# CPU.net
KiCad netlist of a schematic drawn in Altium Designer
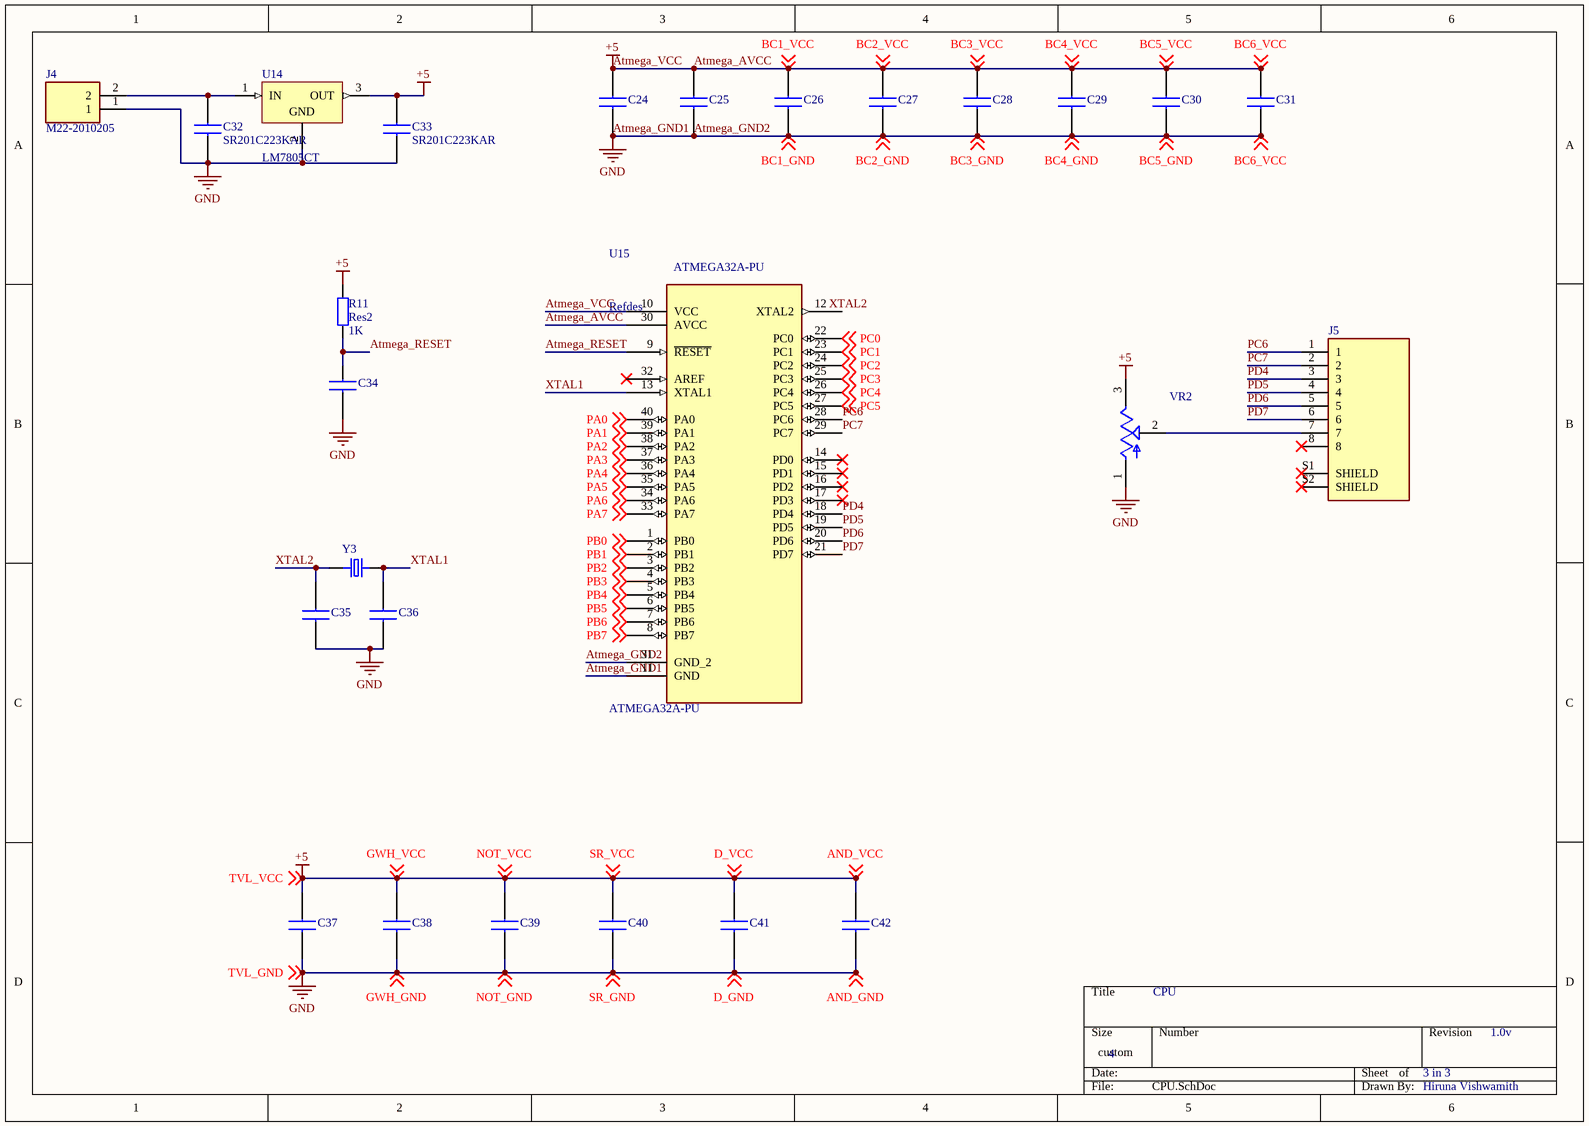
[diagram p0: CPU.SchDoc]

(export (version "E")
  (design (tool "Eeschema 10.0.6"))
  (components
    (comp (ref "C24")
      (value "SR201C223KAR")
      (footprint "AVX-SR20")
      (description "Cap Ceramic 0.022uF 100V X7R 10% Radial 2.54mm 125C Bulk")
      (libsource (lib "SR201C223KAR") (part "SR201C223KAR"))
    )
    (comp (ref "C25")
      (value "SR201C223KAR")
      (footprint "AVX-SR20")
      (description "Cap Ceramic 0.022uF 100V X7R 10% Radial 2.54mm 125C Bulk")
      (libsource (lib "SR201C223KAR") (part "SR201C223KAR"))
    )
    (comp (ref "C26")
      (value "SR201C223KAR")
      (footprint "AVX-SR20")
      (description "Cap Ceramic 0.022uF 100V X7R 10% Radial 2.54mm 125C Bulk")
      (libsource (lib "SR201C223KAR") (part "SR201C223KAR"))
    )
    (comp (ref "C27")
      (value "SR201C223KAR")
      (footprint "AVX-SR20")
      (description "Cap Ceramic 0.022uF 100V X7R 10% Radial 2.54mm 125C Bulk")
      (libsource (lib "SR201C223KAR") (part "SR201C223KAR"))
    )
    (comp (ref "C28")
      (value "SR201C223KAR")
      (footprint "AVX-SR20")
      (description "Cap Ceramic 0.022uF 100V X7R 10% Radial 2.54mm 125C Bulk")
      (libsource (lib "SR201C223KAR") (part "SR201C223KAR"))
    )
    (comp (ref "C29")
      (value "SR201C223KAR")
      (footprint "AVX-SR20")
      (description "Cap Ceramic 0.022uF 100V X7R 10% Radial 2.54mm 125C Bulk")
      (libsource (lib "SR201C223KAR") (part "SR201C223KAR"))
    )
    (comp (ref "C30")
      (value "SR201C223KAR")
      (footprint "AVX-SR20")
      (description "Cap Ceramic 0.022uF 100V X7R 10% Radial 2.54mm 125C Bulk")
      (libsource (lib "SR201C223KAR") (part "SR201C223KAR"))
    )
    (comp (ref "C31")
      (value "SR201C223KAR")
      (footprint "AVX-SR20")
      (description "Cap Ceramic 0.022uF 100V X7R 10% Radial 2.54mm 125C Bulk")
      (libsource (lib "SR201C223KAR") (part "SR201C223KAR"))
    )
    (comp (ref "C32")
      (value "SR201C223KAR")
      (footprint "AVX-SR20")
      (description "Cap Ceramic 0.022uF 100V X7R 10% Radial 2.54mm 125C Bulk")
      (libsource (lib "SR201C223KAR") (part "SR201C223KAR"))
    )
    (comp (ref "C33")
      (value "SR201C223KAR")
      (footprint "AVX-SR20")
      (description "Cap Ceramic 0.022uF 100V X7R 10% Radial 2.54mm 125C Bulk")
      (libsource (lib "SR201C223KAR") (part "SR201C223KAR"))
    )
    (comp (ref "C34")
      (value "SR201C223KAR")
      (footprint "AVX-SR20")
      (description "Cap Ceramic 0.022uF 100V X7R 10% Radial 2.54mm 125C Bulk")
      (libsource (lib "SR201C223KAR") (part "SR201C223KAR"))
    )
    (comp (ref "C35")
      (value "SR201C223KAR")
      (footprint "AVX-SR20")
      (description "Cap Ceramic 0.022uF 100V X7R 10% Radial 2.54mm 125C Bulk")
      (libsource (lib "SR201C223KAR") (part "SR201C223KAR"))
    )
    (comp (ref "C36")
      (value "SR201C223KAR")
      (footprint "AVX-SR20")
      (description "Cap Ceramic 0.022uF 100V X7R 10% Radial 2.54mm 125C Bulk")
      (libsource (lib "SR201C223KAR") (part "SR201C223KAR"))
    )
    (comp (ref "C37")
      (value "SR201C223KAR")
      (footprint "AVX-SR20")
      (description "Cap Ceramic 0.022uF 100V X7R 10% Radial 2.54mm 125C Bulk")
      (libsource (lib "SR201C223KAR") (part "SR201C223KAR"))
    )
    (comp (ref "C38")
      (value "SR201C223KAR")
      (footprint "AVX-SR20")
      (description "Cap Ceramic 0.022uF 100V X7R 10% Radial 2.54mm 125C Bulk")
      (libsource (lib "SR201C223KAR") (part "SR201C223KAR"))
    )
    (comp (ref "C39")
      (value "SR201C223KAR")
      (footprint "AVX-SR20")
      (description "Cap Ceramic 0.022uF 100V X7R 10% Radial 2.54mm 125C Bulk")
      (libsource (lib "SR201C223KAR") (part "SR201C223KAR"))
    )
    (comp (ref "C40")
      (value "SR201C223KAR")
      (footprint "AVX-SR20")
      (description "Cap Ceramic 0.022uF 100V X7R 10% Radial 2.54mm 125C Bulk")
      (libsource (lib "SR201C223KAR") (part "SR201C223KAR"))
    )
    (comp (ref "C41")
      (value "SR201C223KAR")
      (footprint "AVX-SR20")
      (description "Cap Ceramic 0.022uF 100V X7R 10% Radial 2.54mm 125C Bulk")
      (libsource (lib "SR201C223KAR") (part "SR201C223KAR"))
    )
    (comp (ref "C42")
      (value "SR201C223KAR")
      (footprint "AVX-SR20")
      (description "Cap Ceramic 0.022uF 100V X7R 10% Radial 2.54mm 125C Bulk")
      (libsource (lib "SR201C223KAR") (part "SR201C223KAR"))
    )
    (comp (ref "J4")
      (value "M22-2010205")
      (footprint "HDRV2W50P0X200_1X2_400X200X525P")
      (fields (field (name "MOUSER PART NUMBER") "855-M22-2010205"))
      (libsource (lib "M22-2010205") (part "M22-2010205"))
    )
    (comp (ref "J5")
      (value "59453-082110EDHLF")
      (footprint "AMPHENOL_59453-082110EDHLF")
      (fields (field (name "MF") "Amphenol ICC (FCI)"))
      (libsource (lib "59453-082110EDHLF") (part "59453-082110EDHLF"))
    )
    (comp (ref "R11")
      (value "Res2")
      (footprint "AXIAL-0.4")
      (description "Resistor")
      (fields (field (name "ALTIUM_VALUE") "1K") (field (name "PUBLISHER") "Altium Limited"))
      (libsource (lib "Miscellaneous Devices") (part "Res2"))
    )
    (comp (ref "U14")
      (value "LM7805CT")
      (footprint "FAIR-TO-220-3")
      (description "Positive Voltage Regulator, 5 V, 1 A, -40 to 125 degC, 3-Pin TO-220, RoHS, Tube")
      (fields (field (name "MANUFACTURER") "FairchildSemiconductor"))
      (libsource (lib "Altium Content Vault") (part "FAIR-LM7805CT-TO220-3"))
    )
    (comp (ref "U15")
      (value "ATMEGA32A-PU")
      (footprint "DIP254P1524X482-40")
      (description "AVR AVRÂ® ATmega Microcontroller IC 8-Bit 16MHz 32KB (16K x 16) FLASH 40-PDIP")
      (fields (field (name "MF") "Microchip"))
      (libsource (lib "ATMEGA32A-PU") (part "ATMEGA32A-PU"))
    )
    (comp (ref "VR2")
      (value "3362P-1-253LF")
      (footprint "TRIM_3362P-1-253LF")
      (description "25 kOhms 0.5W, 1/2W PC Pins Through Hole Trimmer Potentiometer Cermet 1 Turn Top Adjustment")
      (fields (field (name "MF") "Bourns"))
      (libsource (lib "3362P-1-253LF") (part "3362P-1-253LF"))
    )
    (comp (ref "Y3")
      (value "ECS-240.0001-18-1X")
      (footprint "XTAL_ECS-200-20-1X")
      (description "Crystals / Oscillators / Resonators 24.00014MHz 18pF")
      (fields (field (name "MF") "ECS International"))
      (libsource (lib "ECS-240.0001-18-1X") (part "ECS-240.0001-18-1X"))
    )
  )
  (nets
    (net (code "1") (name "+5") (class "Default")
      (node (ref "C24") (pin "1") (pinfunction "1_1") (pintype "passive"))
      (node (ref "C24") (pin "2") (pinfunction "2_2") (pintype "passive"))
      (node (ref "C25") (pin "1") (pinfunction "1_1") (pintype "passive"))
      (node (ref "C25") (pin "2") (pinfunction "2_2") (pintype "passive"))
      (node (ref "C26") (pin "1") (pinfunction "1_1") (pintype "passive"))
      (node (ref "C26") (pin "2") (pinfunction "2_2") (pintype "passive"))
      (node (ref "C27") (pin "1") (pinfunction "1_1") (pintype "passive"))
      (node (ref "C27") (pin "2") (pinfunction "2_2") (pintype "passive"))
      (node (ref "C28") (pin "1") (pinfunction "1_1") (pintype "passive"))
      (node (ref "C28") (pin "2") (pinfunction "2_2") (pintype "passive"))
      (node (ref "C29") (pin "1") (pinfunction "1_1") (pintype "passive"))
      (node (ref "C29") (pin "2") (pinfunction "2_2") (pintype "passive"))
      (node (ref "C30") (pin "1") (pinfunction "1_1") (pintype "passive"))
      (node (ref "C30") (pin "2") (pinfunction "2_2") (pintype "passive"))
      (node (ref "C31") (pin "1") (pinfunction "1_1") (pintype "passive"))
      (node (ref "C31") (pin "2") (pinfunction "2_2") (pintype "passive"))
      (node (ref "C32") (pin "1") (pinfunction "1_1") (pintype "passive"))
      (node (ref "C33") (pin "1") (pinfunction "1_1") (pintype "passive"))
      (node (ref "C33") (pin "2") (pinfunction "2_2") (pintype "passive"))
      (node (ref "C34") (pin "2") (pinfunction "2_2") (pintype "passive"))
      (node (ref "C35") (pin "1") (pinfunction "1_1") (pintype "passive"))
      (node (ref "C36") (pin "1") (pinfunction "1_1") (pintype "passive"))
      (node (ref "C37") (pin "1") (pinfunction "1_1") (pintype "passive"))
      (node (ref "C37") (pin "2") (pinfunction "2_2") (pintype "passive"))
      (node (ref "C38") (pin "1") (pinfunction "1_1") (pintype "passive"))
      (node (ref "C38") (pin "2") (pinfunction "2_2") (pintype "passive"))
      (node (ref "C39") (pin "1") (pinfunction "1_1") (pintype "passive"))
      (node (ref "C39") (pin "2") (pinfunction "2_2") (pintype "passive"))
      (node (ref "C40") (pin "1") (pinfunction "1_1") (pintype "passive"))
      (node (ref "C40") (pin "2") (pinfunction "2_2") (pintype "passive"))
      (node (ref "C41") (pin "1") (pinfunction "1_1") (pintype "passive"))
      (node (ref "C41") (pin "2") (pinfunction "2_2") (pintype "passive"))
      (node (ref "C42") (pin "1") (pinfunction "1_1") (pintype "passive"))
      (node (ref "C42") (pin "2") (pinfunction "2_2") (pintype "passive"))
      (node (ref "J4") (pin "1") (pinfunction "1_1") (pintype "passive"))
      (node (ref "R11") (pin "2") (pinfunction "2_2") (pintype "passive"))
      (node (ref "U14") (pin "2") (pinfunction "GND_2") (pintype "power_in"))
      (node (ref "U14") (pin "3") (pinfunction "OUT_3") (pintype "output"))
      (node (ref "U15") (pin "10") (pinfunction "VCC_10") (pintype "power_in"))
      (node (ref "U15") (pin "11") (pinfunction "GND_11") (pintype "passive"))
      (node (ref "U15") (pin "30") (pinfunction "AVCC_30") (pintype "power_in"))
      (node (ref "U15") (pin "31") (pinfunction "GND_2_31") (pintype "passive"))
      (node (ref "VR2") (pin "1") (pinfunction "CCW_1") (pintype "passive"))
      (node (ref "VR2") (pin "3") (pinfunction "CW_3") (pintype "passive"))
    )
    (net (code "2") (name "/Atmega_RESET") (class "Default")
      (node (ref "C34") (pin "1") (pinfunction "1_1") (pintype "passive"))
      (node (ref "R11") (pin "1") (pinfunction "1_1") (pintype "passive"))
      (node (ref "U15") (pin "9") (pinfunction "~{RESET}_9") (pintype "input"))
    )
    (net (code "3") (name "/PC6") (class "Default")
      (node (ref "J5") (pin "1") (pinfunction "1_1") (pintype "passive"))
      (node (ref "U15") (pin "28") (pinfunction "PC6_28") (pintype "bidirectional"))
    )
    (net (code "4") (name "/PC7") (class "Default")
      (node (ref "J5") (pin "2") (pinfunction "2_2") (pintype "passive"))
      (node (ref "U15") (pin "29") (pinfunction "PC7_29") (pintype "bidirectional"))
    )
    (net (code "5") (name "/PD4") (class "Default")
      (node (ref "J5") (pin "3") (pinfunction "3_3") (pintype "passive"))
      (node (ref "U15") (pin "18") (pinfunction "PD4_18") (pintype "bidirectional"))
    )
    (net (code "6") (name "/PD5") (class "Default")
      (node (ref "J5") (pin "4") (pinfunction "4_4") (pintype "passive"))
      (node (ref "U15") (pin "19") (pinfunction "PD5_19") (pintype "bidirectional"))
    )
    (net (code "7") (name "/PD6") (class "Default")
      (node (ref "J5") (pin "5") (pinfunction "5_5") (pintype "passive"))
      (node (ref "U15") (pin "20") (pinfunction "PD6_20") (pintype "bidirectional"))
    )
    (net (code "8") (name "/PD7") (class "Default")
      (node (ref "J5") (pin "6") (pinfunction "6_6") (pintype "passive"))
      (node (ref "U15") (pin "21") (pinfunction "PD7_21") (pintype "bidirectional"))
    )
    (net (code "9") (name "/XTAL1") (class "Default")
      (node (ref "C36") (pin "2") (pinfunction "2_2") (pintype "passive"))
      (node (ref "U15") (pin "13") (pinfunction "XTAL1_13") (pintype "input"))
      (node (ref "Y3") (pin "2") (pinfunction "2_2") (pintype "passive"))
    )
    (net (code "10") (name "/XTAL2") (class "Default")
      (node (ref "C35") (pin "2") (pinfunction "2_2") (pintype "passive"))
      (node (ref "Y3") (pin "1") (pinfunction "1_1") (pintype "passive"))
    )
    (net (code "11") (name "Net-(U14-IN)") (class "Default")
      (node (ref "C32") (pin "2") (pinfunction "2_2") (pintype "passive"))
      (node (ref "J4") (pin "2") (pinfunction "2_2") (pintype "passive"))
      (node (ref "U14") (pin "1") (pinfunction "IN_1") (pintype "input"))
    )
    (net (code "12") (name "Net-(VR2-WIPER)") (class "Default")
      (node (ref "J5") (pin "7") (pinfunction "7_7") (pintype "passive"))
      (node (ref "VR2") (pin "2") (pinfunction "WIPER_2") (pintype "passive"))
    )
    (net (code "13") (name "PA0") (class "Default")
      (node (ref "U15") (pin "40") (pinfunction "PA0_40") (pintype "bidirectional"))
    )
    (net (code "14") (name "PA1") (class "Default")
      (node (ref "U15") (pin "39") (pinfunction "PA1_39") (pintype "bidirectional"))
    )
    (net (code "15") (name "PA2") (class "Default")
      (node (ref "U15") (pin "38") (pinfunction "PA2_38") (pintype "bidirectional"))
    )
    (net (code "16") (name "PA3") (class "Default")
      (node (ref "U15") (pin "37") (pinfunction "PA3_37") (pintype "bidirectional"))
    )
    (net (code "17") (name "PA4") (class "Default")
      (node (ref "U15") (pin "36") (pinfunction "PA4_36") (pintype "bidirectional"))
    )
    (net (code "18") (name "PA5") (class "Default")
      (node (ref "U15") (pin "35") (pinfunction "PA5_35") (pintype "bidirectional"))
    )
    (net (code "19") (name "PA6") (class "Default")
      (node (ref "U15") (pin "34") (pinfunction "PA6_34") (pintype "bidirectional"))
    )
    (net (code "20") (name "PA7") (class "Default")
      (node (ref "U15") (pin "33") (pinfunction "PA7_33") (pintype "bidirectional"))
    )
    (net (code "21") (name "PB0") (class "Default")
      (node (ref "U15") (pin "1") (pinfunction "PB0_1") (pintype "bidirectional"))
    )
    (net (code "22") (name "PB1") (class "Default")
      (node (ref "U15") (pin "2") (pinfunction "PB1_2") (pintype "bidirectional"))
    )
    (net (code "23") (name "PB2") (class "Default")
      (node (ref "U15") (pin "3") (pinfunction "PB2_3") (pintype "bidirectional"))
    )
    (net (code "24") (name "PB3") (class "Default")
      (node (ref "U15") (pin "4") (pinfunction "PB3_4") (pintype "bidirectional"))
    )
    (net (code "25") (name "PB4") (class "Default")
      (node (ref "U15") (pin "5") (pinfunction "PB4_5") (pintype "bidirectional"))
    )
    (net (code "26") (name "PB5") (class "Default")
      (node (ref "U15") (pin "6") (pinfunction "PB5_6") (pintype "bidirectional"))
    )
    (net (code "27") (name "PB6") (class "Default")
      (node (ref "U15") (pin "7") (pinfunction "PB6_7") (pintype "bidirectional"))
    )
    (net (code "28") (name "PB7") (class "Default")
      (node (ref "U15") (pin "8") (pinfunction "PB7_8") (pintype "bidirectional"))
    )
    (net (code "29") (name "PC0") (class "Default")
      (node (ref "U15") (pin "22") (pinfunction "PC0_22") (pintype "bidirectional"))
    )
    (net (code "30") (name "PC1") (class "Default")
      (node (ref "U15") (pin "23") (pinfunction "PC1_23") (pintype "bidirectional"))
    )
    (net (code "31") (name "PC2") (class "Default")
      (node (ref "U15") (pin "24") (pinfunction "PC2_24") (pintype "bidirectional"))
    )
    (net (code "32") (name "PC3") (class "Default")
      (node (ref "U15") (pin "25") (pinfunction "PC3_25") (pintype "bidirectional"))
    )
    (net (code "33") (name "PC4") (class "Default")
      (node (ref "U15") (pin "26") (pinfunction "PC4_26") (pintype "bidirectional"))
    )
    (net (code "34") (name "PC5") (class "Default")
      (node (ref "U15") (pin "27") (pinfunction "PC5_27") (pintype "bidirectional"))
    )
    (net (code "35") (name "unconnected-(J5-Pad8)") (class "Default")
      (node (ref "J5") (pin "8") (pinfunction "8_8") (pintype "passive+no_connect"))
    )
    (net (code "36") (name "unconnected-(J5-SHIELD-PadS1)") (class "Default")
      (node (ref "J5") (pin "S1") (pinfunction "SHIELD_S1") (pintype "passive+no_connect"))
    )
    (net (code "37") (name "unconnected-(J5-SHIELD-PadS2)") (class "Default")
      (node (ref "J5") (pin "S2") (pinfunction "SHIELD_S2") (pintype "passive+no_connect"))
    )
    (net (code "38") (name "unconnected-(U15-AREF-Pad32)") (class "Default")
      (node (ref "U15") (pin "32") (pinfunction "AREF_32") (pintype "input+no_connect"))
    )
    (net (code "39") (name "unconnected-(U15-PD0-Pad14)") (class "Default")
      (node (ref "U15") (pin "14") (pinfunction "PD0_14") (pintype "bidirectional+no_connect"))
    )
    (net (code "40") (name "unconnected-(U15-PD1-Pad15)") (class "Default")
      (node (ref "U15") (pin "15") (pinfunction "PD1_15") (pintype "bidirectional+no_connect"))
    )
    (net (code "41") (name "unconnected-(U15-PD2-Pad16)") (class "Default")
      (node (ref "U15") (pin "16") (pinfunction "PD2_16") (pintype "bidirectional+no_connect"))
    )
    (net (code "42") (name "unconnected-(U15-PD3-Pad17)") (class "Default")
      (node (ref "U15") (pin "17") (pinfunction "PD3_17") (pintype "bidirectional+no_connect"))
    )
    (net (code "43") (name "unconnected-(U15-XTAL2-Pad12)") (class "Default")
      (node (ref "U15") (pin "12") (pinfunction "XTAL2_12") (pintype "output"))
    )
  )
)
